# DM1098FFC_TopLevel.net
KiCad netlist of a schematic drawn in Altium Designer
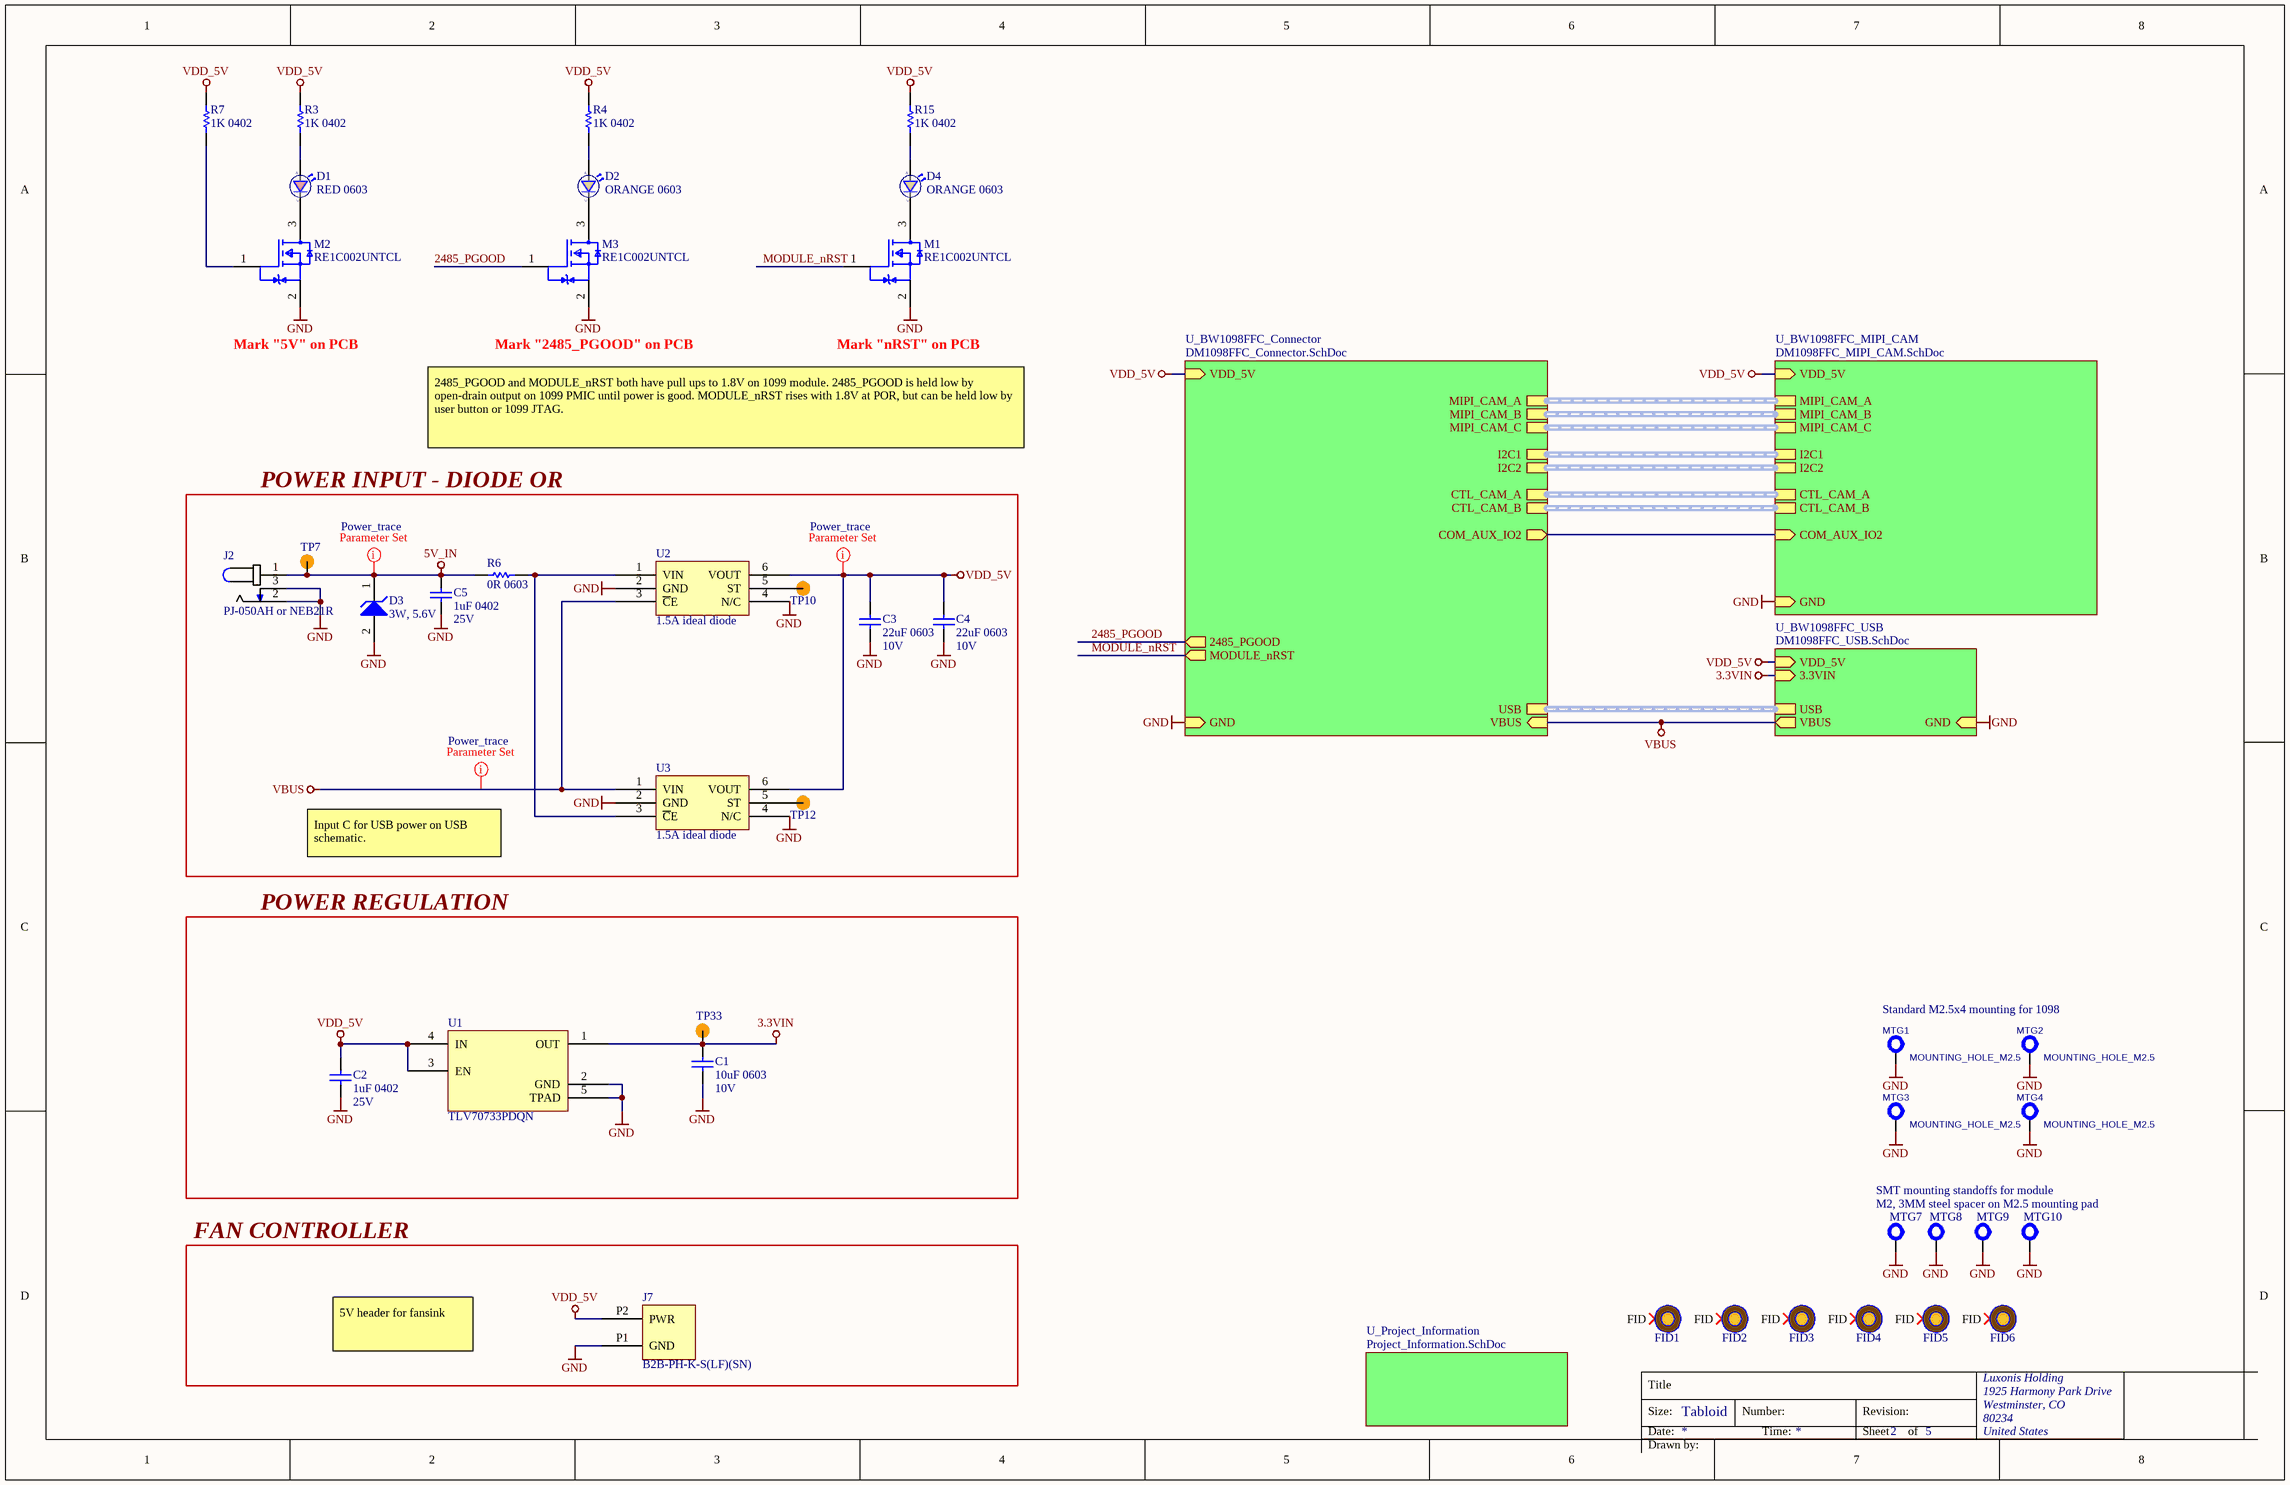
[diagram p0: DM1098FFC_TopLevel.SchDoc]

(export (version "E")
  (design (tool "Eeschema 10.0.6"))
  (components
    (comp (ref "C1")
      (value "10uF 0603")
      (footprint "CAP_Altium_Vault_Generic:CAPC0603(1608)100_N")
      (description "CAP CER 10UF 10V X5R 0603 20%")
      (fields (field (name "TOLERANCE") "20%") (field (name "VOLTAGE RATING") "10V"))
      (libsource (lib "LuxonisMaster") (part "GRM188R61A106ME69D"))
    )
    (comp (ref "C2")
      (value "1uF 0402")
      (footprint "CAP_Altium_Vault_Generic:CAPC0402(1005)70_N")
      (description "CAP CER 1UF 25V X5R 0402 10%")
      (fields
        (field (name "TOLERANCE") "10%")
        (field (name "VOLTAGE") "25V")
        (field (name "VOLTAGE RATING") "25V")
      )
      (libsource (lib "LuxonisMaster") (part "GRM155R61E105KA12D"))
    )
    (comp (ref "C3")
      (value "22uF 0603")
      (footprint "CAP_Altium_Vault_Generic:CAPC0603(1608)100_N")
      (description "CAP CER 22UF 10V X5R 0603 20%")
      (fields (field (name "TOLERANCE") "20%") (field (name "VOLTAGE RATING") "10V"))
      (libsource (lib "LuxonisMaster") (part "GRM188R61A226ME15D"))
    )
    (comp (ref "C4")
      (value "22uF 0603")
      (footprint "CAP_Altium_Vault_Generic:CAPC0603(1608)100_N")
      (description "CAP CER 22UF 10V X5R 0603 20%")
      (fields (field (name "TOLERANCE") "20%") (field (name "VOLTAGE RATING") "10V"))
      (libsource (lib "LuxonisMaster") (part "GRM188R61A226ME15D"))
    )
    (comp (ref "C5")
      (value "1uF 0402")
      (footprint "CAP_Altium_Vault_Generic:CAPC0402(1005)70_N")
      (description "CAP CER 1UF 25V X5R 0402 10%")
      (fields
        (field (name "TOLERANCE") "10%")
        (field (name "VOLTAGE") "25V")
        (field (name "VOLTAGE RATING") "25V")
      )
      (libsource (lib "LuxonisMaster") (part "GRM155R61E105KA12D"))
    )
    (comp (ref "D1")
      (value "RED 0603")
      (footprint "LuxonisMaster:SML_D1xx8W")
      (description "LED RED DIFFUSED 0603 SMD Red 620nm LED Indication - Discrete 2.2V 0603 (1608 Metric)")
      (libsource (lib "LuxonisMaster") (part "SML-D12U8WT86"))
    )
    (comp (ref "D2")
      (value "ORANGE 0603")
      (footprint "LuxonisMaster:SML_D1xx8W")
      (description "LED ORANGE DIFFUSED 0603 SMD Orange 605nm LED Indication - Discrete 2.2V 0603 (1608 Metric)")
      (libsource (lib "LuxonisMaster") (part "SML-D12D8WT86"))
    )
    (comp (ref "D3")
      (value "3W, 5.6V")
      (footprint "DM1092_R0M0E0:1SMB5919BT3G")
      (description "DIODE ZENER 5.6V 3W SMB")
      (fields (field (name "TOLERANCE") "5%"))
      (libsource (lib "DM1092_R0M0E0") (part "1SMB5919BT3G"))
    )
    (comp (ref "D4")
      (value "ORANGE 0603")
      (footprint "LuxonisMaster:SML_D1xx8W")
      (description "LED ORANGE DIFFUSED 0603 SMD Orange 605nm LED Indication - Discrete 2.2V 0603 (1608 Metric)")
      (libsource (lib "LuxonisMaster") (part "SML-D12D8WT86"))
    )
    (comp (ref "FID1")
      (value "FIDUCIAL_ROUND_1MM")
      (footprint "LuxonisMaster:FIDUCIAL_ROUND_1MM")
      (description "Fiducial with various available footprints")
      (libsource (lib "LuxonisMaster") (part "FIDUCIAL"))
    )
    (comp (ref "FID2")
      (value "FIDUCIAL_ROUND_1MM")
      (footprint "LuxonisMaster:FIDUCIAL_ROUND_1MM")
      (description "Fiducial with various available footprints")
      (libsource (lib "LuxonisMaster") (part "FIDUCIAL"))
    )
    (comp (ref "FID3")
      (value "FIDUCIAL_ROUND_1MM")
      (footprint "LuxonisMaster:FIDUCIAL_ROUND_1MM")
      (description "Fiducial with various available footprints")
      (libsource (lib "LuxonisMaster") (part "FIDUCIAL"))
    )
    (comp (ref "FID4")
      (value "FIDUCIAL_ROUND_1MM")
      (footprint "LuxonisMaster:FIDUCIAL_ROUND_1MM")
      (description "Fiducial with various available footprints")
      (libsource (lib "LuxonisMaster") (part "FIDUCIAL"))
    )
    (comp (ref "FID5")
      (value "FIDUCIAL_ROUND_1MM")
      (footprint "LuxonisMaster:FIDUCIAL_ROUND_1MM")
      (description "Fiducial with various available footprints")
      (libsource (lib "LuxonisMaster") (part "FIDUCIAL"))
    )
    (comp (ref "FID6")
      (value "FIDUCIAL_ROUND_1MM")
      (footprint "LuxonisMaster:FIDUCIAL_ROUND_1MM")
      (description "Fiducial with various available footprints")
      (libsource (lib "LuxonisMaster") (part "FIDUCIAL"))
    )
    (comp (ref "J2")
      (value "PJ-050AH or NEB21R")
      (footprint "LuxonisMaster:PJ-050AH/NEB21R_COMBO")
      (description "CONN POWER PIN 2 POS RA PTH Barrel jack 2.1mm x 5.5mm combo footprint")
      (libsource (lib "LuxonisMaster") (part "PJ-050AH/NEB21R_COMBO"))
    )
    (comp (ref "J7")
      (value "B2B-PH-K-S(LF)(SN)")
      (footprint "LuxonisMaster:B2B-PH-K-S(LF)(SN)")
      (description "CONN HEADER VERT 2POS 2MM")
      (libsource (lib "LuxonisMaster") (part "B2B-PH-K-S(LF)(SN)"))
    )
    (comp (ref "M1")
      (value "RE1C002UNTCL")
      (footprint "LuxonisMaster:RE1C002UNTCL")
      (description "MOSFET N-CH 20V 0.2A EMT3")
      (libsource (lib "LuxonisMaster") (part "RE1C002UNTCL"))
    )
    (comp (ref "M2")
      (value "RE1C002UNTCL")
      (footprint "LuxonisMaster:RE1C002UNTCL")
      (description "MOSFET N-CH 20V 0.2A EMT3")
      (libsource (lib "LuxonisMaster") (part "RE1C002UNTCL"))
    )
    (comp (ref "M3")
      (value "RE1C002UNTCL")
      (footprint "LuxonisMaster:RE1C002UNTCL")
      (description "MOSFET N-CH 20V 0.2A EMT3")
      (libsource (lib "LuxonisMaster") (part "RE1C002UNTCL"))
    )
    (comp (ref "MTG1")
      (value "MOUNTING_HOLE_M2.5")
      (footprint "LuxonisMaster:MOUNTING_HOLE_M2.5")
      (description "=CurrentFootprint")
      (libsource (lib "LuxonisMaster") (part "MP_Mounting-Holes"))
    )
    (comp (ref "MTG2")
      (value "MOUNTING_HOLE_M2.5")
      (footprint "LuxonisMaster:MOUNTING_HOLE_M2.5")
      (description "=CurrentFootprint")
      (libsource (lib "LuxonisMaster") (part "MP_Mounting-Holes"))
    )
    (comp (ref "MTG3")
      (value "MOUNTING_HOLE_M2.5")
      (footprint "LuxonisMaster:MOUNTING_HOLE_M2.5")
      (description "=CurrentFootprint")
      (libsource (lib "LuxonisMaster") (part "MP_Mounting-Holes"))
    )
    (comp (ref "MTG4")
      (value "MOUNTING_HOLE_M2.5")
      (footprint "LuxonisMaster:MOUNTING_HOLE_M2.5")
      (description "=CurrentFootprint")
      (libsource (lib "LuxonisMaster") (part "MP_Mounting-Holes"))
    )
    (comp (ref "MTG7")
      (value "M2, 3MM steel spacer on M2.5 mounting pad")
      (footprint "LuxonisMaster:9774030243R")
      (description "MP ROUND STANDOFF M2X0.4 STEEL 3MM")
      (libsource (lib "LuxonisMaster") (part "9774030243R"))
    )
    (comp (ref "MTG8")
      (value "M2, 3MM steel spacer on M2.5 mounting pad")
      (footprint "LuxonisMaster:9774030243R")
      (description "MP ROUND STANDOFF M2X0.4 STEEL 3MM")
      (libsource (lib "LuxonisMaster") (part "9774030243R"))
    )
    (comp (ref "MTG9")
      (value "M2, 3MM steel spacer on M2.5 mounting pad")
      (footprint "LuxonisMaster:9774030243R")
      (description "MP ROUND STANDOFF M2X0.4 STEEL 3MM")
      (libsource (lib "LuxonisMaster") (part "9774030243R"))
    )
    (comp (ref "MTG10")
      (value "M2, 3MM steel spacer on M2.5 mounting pad")
      (footprint "LuxonisMaster:9774030243R")
      (description "MP ROUND STANDOFF M2X0.4 STEEL 3MM")
      (libsource (lib "LuxonisMaster") (part "9774030243R"))
    )
    (comp (ref "R3")
      (value "1K 0402")
      (footprint "RES_Altium_Vault_Generic:RESC0402(1005)_N")
      (fields (field (name "TOLERANCE") "1%"))
      (libsource (lib "LuxonisMaster") (part "RC0402FR-071KL"))
    )
    (comp (ref "R4")
      (value "1K 0402")
      (footprint "RES_Altium_Vault_Generic:RESC0402(1005)_N")
      (fields (field (name "TOLERANCE") "1%"))
      (libsource (lib "LuxonisMaster") (part "RC0402FR-071KL"))
    )
    (comp (ref "R6")
      (value "0R 0603")
      (footprint "RES_Altium_Vault_Generic:RESC0603(1608)_N")
      (fields (field (name "TOLERANCE") "5%"))
      (libsource (lib "LuxonisMaster") (part "CRCW06030000Z0EA"))
    )
    (comp (ref "R7")
      (value "1K 0402")
      (footprint "RES_Altium_Vault_Generic:RESC0402(1005)_N")
      (fields (field (name "TOLERANCE") "1%"))
      (libsource (lib "LuxonisMaster") (part "RC0402FR-071KL"))
    )
    (comp (ref "R15")
      (value "1K 0402")
      (footprint "RES_Altium_Vault_Generic:RESC0402(1005)_N")
      (fields (field (name "TOLERANCE") "1%"))
      (libsource (lib "LuxonisMaster") (part "RC0402FR-071KL"))
    )
    (comp (ref "TP7")
      (value "TP100_200_NS")
      (footprint "LuxonisMaster:TP100_200_NS")
      (libsource (lib "LuxonisMaster") (part "TEST_POINT"))
    )
    (comp (ref "TP10")
      (value "TP100_200_NS")
      (footprint "LuxonisMaster:TP100_200_NS")
      (libsource (lib "LuxonisMaster") (part "TEST_POINT"))
    )
    (comp (ref "TP12")
      (value "TP100_200_NS")
      (footprint "LuxonisMaster:TP100_200_NS")
      (libsource (lib "LuxonisMaster") (part "TEST_POINT"))
    )
    (comp (ref "TP33")
      (value "TP100_200_NS")
      (footprint "LuxonisMaster:TP100_200_NS")
      (libsource (lib "LuxonisMaster") (part "TEST_POINT"))
    )
    (comp (ref "U1")
      (value "TLV70733PDQN")
      (footprint "LuxonisMaster:TLV70733PDQN")
      (description "IC REG LINEAR 3.3V 200MA 4X2SON Linear Voltage Regulator IC  1 Output  200mA 4-X2SON (1x1)")
      (libsource (lib "LuxonisMaster") (part "TLV70733PDQN"))
    )
    (comp (ref "U2")
      (value "1.5A ideal diode")
      (footprint "LuxonisMaster:LM66100DCKR")
      (description "IC OR CTRLR IDEAL DIODE SC70-6")
      (libsource (lib "LuxonisMaster") (part "LM66100DCKR"))
    )
    (comp (ref "U3")
      (value "1.5A ideal diode")
      (footprint "LuxonisMaster:LM66100DCKR")
      (description "IC OR CTRLR IDEAL DIODE SC70-6")
      (libsource (lib "LuxonisMaster") (part "LM66100DCKR"))
    )
  )
  (nets
    (net (code "1") (name "/2485_PGOOD") (class "Default")
      (node (ref "M3") (pin "1") (pinfunction "Gate_1") (pintype "passive"))
    )
    (net (code "10") (name "/MODULE_nRST") (class "Default")
      (node (ref "M1") (pin "1") (pinfunction "Gate_1") (pintype "passive"))
    )
    (net (code "12") (name "3.3VIN") (class "Default")
      (node (ref "C1") (pin "2") (pinfunction "2_2") (pintype "passive"))
      (node (ref "TP33") (pin "1") (pintype "passive"))
      (node (ref "U1") (pin "1") (pinfunction "OUT_1") (pintype "power_in"))
    )
    (net (code "13") (name "5V_IN") (class "Default")
      (node (ref "C5") (pin "2") (pinfunction "2_2") (pintype "passive"))
      (node (ref "D3") (pin "1") (pinfunction "K_1") (pintype "passive"))
      (node (ref "J2") (pin "1") (pinfunction "1_1") (pintype "passive"))
      (node (ref "R6") (pin "1") (pinfunction "1_1") (pintype "passive"))
      (node (ref "TP7") (pin "1") (pintype "passive"))
    )
    (net (code "14") (name "GND") (class "Default")
      (node (ref "C1") (pin "1") (pinfunction "1_1") (pintype "passive"))
      (node (ref "C2") (pin "1") (pinfunction "1_1") (pintype "passive"))
      (node (ref "C3") (pin "1") (pinfunction "1_1") (pintype "passive"))
      (node (ref "C4") (pin "1") (pinfunction "1_1") (pintype "passive"))
      (node (ref "C5") (pin "1") (pinfunction "1_1") (pintype "passive"))
      (node (ref "D3") (pin "2") (pinfunction "A_2") (pintype "passive"))
      (node (ref "J2") (pin "2") (pinfunction "2_2") (pintype "passive"))
      (node (ref "J2") (pin "3") (pinfunction "3_3") (pintype "passive"))
      (node (ref "J7") (pin "P1") (pinfunction "GND_P1") (pintype "passive"))
      (node (ref "M1") (pin "2") (pinfunction "Source_2") (pintype "passive"))
      (node (ref "M2") (pin "2") (pinfunction "Source_2") (pintype "passive"))
      (node (ref "M3") (pin "2") (pinfunction "Source_2") (pintype "passive"))
      (node (ref "MTG1") (pin "1") (pintype "passive"))
      (node (ref "MTG10") (pin "1") (pintype "passive"))
      (node (ref "MTG2") (pin "1") (pintype "passive"))
      (node (ref "MTG3") (pin "1") (pintype "passive"))
      (node (ref "MTG4") (pin "1") (pintype "passive"))
      (node (ref "MTG7") (pin "1") (pintype "passive"))
      (node (ref "MTG8") (pin "1") (pintype "passive"))
      (node (ref "MTG9") (pin "1") (pintype "passive"))
      (node (ref "U1") (pin "2") (pinfunction "GND_2") (pintype "power_in"))
      (node (ref "U1") (pin "5") (pinfunction "TPAD_5") (pintype "passive"))
      (node (ref "U2") (pin "2") (pinfunction "GND_2") (pintype "passive"))
      (node (ref "U2") (pin "4") (pinfunction "N/C_4") (pintype "passive"))
      (node (ref "U3") (pin "2") (pinfunction "GND_2") (pintype "passive"))
      (node (ref "U3") (pin "4") (pinfunction "N/C_4") (pintype "passive"))
    )
    (net (code "15") (name "Net-(D1-A)") (class "Default")
      (node (ref "D1") (pin "2") (pinfunction "A_2") (pintype "passive"))
      (node (ref "R3") (pin "1") (pinfunction "1_1") (pintype "passive"))
    )
    (net (code "16") (name "Net-(D1-C)") (class "Default")
      (node (ref "D1") (pin "1") (pinfunction "C_1") (pintype "passive"))
      (node (ref "M2") (pin "3") (pinfunction "Drain_3") (pintype "passive"))
    )
    (net (code "17") (name "Net-(D2-A)") (class "Default")
      (node (ref "D2") (pin "2") (pinfunction "A_2") (pintype "passive"))
      (node (ref "R4") (pin "1") (pinfunction "1_1") (pintype "passive"))
    )
    (net (code "18") (name "Net-(D2-C)") (class "Default")
      (node (ref "D2") (pin "1") (pinfunction "C_1") (pintype "passive"))
      (node (ref "M3") (pin "3") (pinfunction "Drain_3") (pintype "passive"))
    )
    (net (code "19") (name "Net-(D4-A)") (class "Default")
      (node (ref "D4") (pin "2") (pinfunction "A_2") (pintype "passive"))
      (node (ref "R15") (pin "1") (pinfunction "1_1") (pintype "passive"))
    )
    (net (code "20") (name "Net-(D4-C)") (class "Default")
      (node (ref "D4") (pin "1") (pinfunction "C_1") (pintype "passive"))
      (node (ref "M1") (pin "3") (pinfunction "Drain_3") (pintype "passive"))
    )
    (net (code "21") (name "Net-(M2-Gate)") (class "Default")
      (node (ref "M2") (pin "1") (pinfunction "Gate_1") (pintype "passive"))
      (node (ref "R7") (pin "1") (pinfunction "1_1") (pintype "passive"))
    )
    (net (code "22") (name "Net-(U2-ST)") (class "Default")
      (node (ref "TP10") (pin "1") (pintype "passive"))
      (node (ref "U2") (pin "5") (pinfunction "ST_5") (pintype "passive"))
    )
    (net (code "23") (name "Net-(U2-VIN)") (class "Default")
      (node (ref "R6") (pin "2") (pinfunction "2_2") (pintype "passive"))
      (node (ref "U2") (pin "1") (pinfunction "VIN_1") (pintype "passive"))
      (node (ref "U3") (pin "3") (pinfunction "~{C}E_3") (pintype "passive"))
    )
    (net (code "24") (name "Net-(U3-ST)") (class "Default")
      (node (ref "TP12") (pin "1") (pintype "passive"))
      (node (ref "U3") (pin "5") (pinfunction "ST_5") (pintype "passive"))
    )
    (net (code "25") (name "VBUS") (class "Default")
      (node (ref "U2") (pin "3") (pinfunction "~{C}E_3") (pintype "passive"))
      (node (ref "U3") (pin "1") (pinfunction "VIN_1") (pintype "passive"))
    )
    (net (code "26") (name "VDD_5V") (class "Default")
      (node (ref "C2") (pin "2") (pinfunction "2_2") (pintype "passive"))
      (node (ref "C3") (pin "2") (pinfunction "2_2") (pintype "passive"))
      (node (ref "C4") (pin "2") (pinfunction "2_2") (pintype "passive"))
      (node (ref "J7") (pin "P2") (pinfunction "PWR_P2") (pintype "passive"))
      (node (ref "R15") (pin "2") (pinfunction "2_2") (pintype "passive"))
      (node (ref "R3") (pin "2") (pinfunction "2_2") (pintype "passive"))
      (node (ref "R4") (pin "2") (pinfunction "2_2") (pintype "passive"))
      (node (ref "R7") (pin "2") (pinfunction "2_2") (pintype "passive"))
      (node (ref "U1") (pin "3") (pinfunction "EN_3") (pintype "power_in"))
      (node (ref "U1") (pin "4") (pinfunction "IN_4") (pintype "power_in"))
      (node (ref "U2") (pin "6") (pinfunction "VOUT_6") (pintype "passive"))
      (node (ref "U3") (pin "6") (pinfunction "VOUT_6") (pintype "passive"))
    )
    (net (code "27") (name "unconnected-(FID1-PadFID)") (class "Default")
      (node (ref "FID1") (pin "FID") (pinfunction "FID_FID") (pintype "input+no_connect"))
    )
    (net (code "28") (name "unconnected-(FID2-PadFID)") (class "Default")
      (node (ref "FID2") (pin "FID") (pinfunction "FID_FID") (pintype "input+no_connect"))
    )
    (net (code "29") (name "unconnected-(FID3-PadFID)") (class "Default")
      (node (ref "FID3") (pin "FID") (pinfunction "FID_FID") (pintype "input+no_connect"))
    )
    (net (code "30") (name "unconnected-(FID4-PadFID)") (class "Default")
      (node (ref "FID4") (pin "FID") (pinfunction "FID_FID") (pintype "input+no_connect"))
    )
    (net (code "31") (name "unconnected-(FID5-PadFID)") (class "Default")
      (node (ref "FID5") (pin "FID") (pinfunction "FID_FID") (pintype "input+no_connect"))
    )
    (net (code "32") (name "unconnected-(FID6-PadFID)") (class "Default")
      (node (ref "FID6") (pin "FID") (pinfunction "FID_FID") (pintype "input+no_connect"))
    )
  )
)
